# KeyboardMatrix.net
KiCad netlist of a schematic drawn in Altium Designer
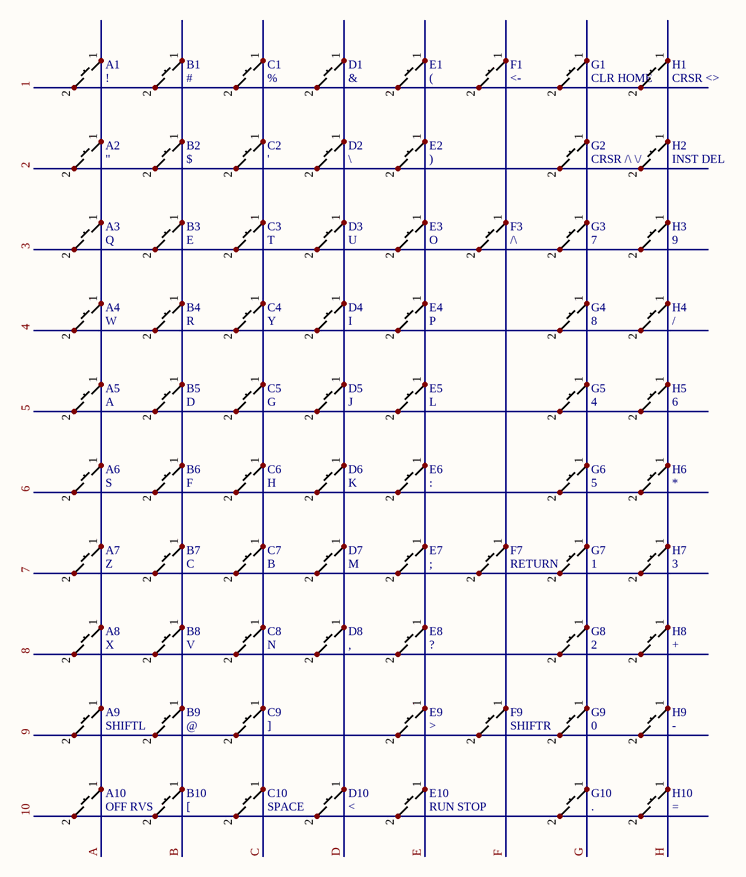
[diagram p0: KeyboardMatrix.SchDoc]

(export (version "E")
  (design (tool "Eeschema 10.0.6"))
  (components
    (comp (ref "A1")
      (value "!")
      (footprint "PET2001NKeyboardSoftButton")
      (libsource (lib "SomeParts") (part "PET2001NKeyboardSoftButton"))
    )
    (comp (ref "A2")
      (value "\"")
      (footprint "PET2001NKeyboardSoftButton")
      (libsource (lib "SomeParts") (part "PET2001NKeyboardSoftButton"))
    )
    (comp (ref "A3")
      (value "Q")
      (footprint "PET2001NKeyboardSoftButton")
      (libsource (lib "SomeParts") (part "PET2001NKeyboardSoftButton"))
    )
    (comp (ref "A4")
      (value "W")
      (footprint "PET2001NKeyboardSoftButton")
      (libsource (lib "SomeParts") (part "PET2001NKeyboardSoftButton"))
    )
    (comp (ref "A5")
      (value "A")
      (footprint "PET2001NKeyboardSoftButton")
      (libsource (lib "SomeParts") (part "PET2001NKeyboardSoftButton"))
    )
    (comp (ref "A6")
      (value "S")
      (footprint "PET2001NKeyboardSoftButton")
      (libsource (lib "SomeParts") (part "PET2001NKeyboardSoftButton"))
    )
    (comp (ref "A7")
      (value "Z")
      (footprint "PET2001NKeyboardSoftButton")
      (libsource (lib "SomeParts") (part "PET2001NKeyboardSoftButton"))
    )
    (comp (ref "A8")
      (value "X")
      (footprint "PET2001NKeyboardSoftButton")
      (libsource (lib "SomeParts") (part "PET2001NKeyboardSoftButton"))
    )
    (comp (ref "A9")
      (value "SHIFTL")
      (footprint "PET2001NKeyboardSoftButton")
      (libsource (lib "SomeParts") (part "PET2001NKeyboardSoftButton"))
    )
    (comp (ref "A10")
      (value "OFF RVS")
      (footprint "PET2001NKeyboardSoftButton")
      (libsource (lib "SomeParts") (part "PET2001NKeyboardSoftButton"))
    )
    (comp (ref "B1")
      (value "#")
      (footprint "PET2001NKeyboardSoftButton")
      (libsource (lib "SomeParts") (part "PET2001NKeyboardSoftButton"))
    )
    (comp (ref "B2")
      (value "$")
      (footprint "PET2001NKeyboardSoftButton")
      (libsource (lib "SomeParts") (part "PET2001NKeyboardSoftButton"))
    )
    (comp (ref "B3")
      (value "E")
      (footprint "PET2001NKeyboardSoftButton")
      (libsource (lib "SomeParts") (part "PET2001NKeyboardSoftButton"))
    )
    (comp (ref "B4")
      (value "R")
      (footprint "PET2001NKeyboardSoftButton")
      (libsource (lib "SomeParts") (part "PET2001NKeyboardSoftButton"))
    )
    (comp (ref "B5")
      (value "D")
      (footprint "PET2001NKeyboardSoftButton")
      (libsource (lib "SomeParts") (part "PET2001NKeyboardSoftButton"))
    )
    (comp (ref "B6")
      (value "F")
      (footprint "PET2001NKeyboardSoftButton")
      (libsource (lib "SomeParts") (part "PET2001NKeyboardSoftButton"))
    )
    (comp (ref "B7")
      (value "C")
      (footprint "PET2001NKeyboardSoftButton")
      (libsource (lib "SomeParts") (part "PET2001NKeyboardSoftButton"))
    )
    (comp (ref "B8")
      (value "V")
      (footprint "PET2001NKeyboardSoftButton")
      (libsource (lib "SomeParts") (part "PET2001NKeyboardSoftButton"))
    )
    (comp (ref "B9")
      (value "@")
      (footprint "PET2001NKeyboardSoftButton")
      (libsource (lib "SomeParts") (part "PET2001NKeyboardSoftButton"))
    )
    (comp (ref "B10")
      (value "[")
      (footprint "PET2001NKeyboardSoftButton")
      (libsource (lib "SomeParts") (part "PET2001NKeyboardSoftButton"))
    )
    (comp (ref "C1")
      (value "%")
      (footprint "PET2001NKeyboardSoftButton")
      (libsource (lib "SomeParts") (part "PET2001NKeyboardSoftButton"))
    )
    (comp (ref "C2")
      (value "'")
      (footprint "PET2001NKeyboardSoftButton")
      (libsource (lib "SomeParts") (part "PET2001NKeyboardSoftButton"))
    )
    (comp (ref "C3")
      (value "T")
      (footprint "PET2001NKeyboardSoftButton")
      (libsource (lib "SomeParts") (part "PET2001NKeyboardSoftButton"))
    )
    (comp (ref "C4")
      (value "Y")
      (footprint "PET2001NKeyboardSoftButton")
      (libsource (lib "SomeParts") (part "PET2001NKeyboardSoftButton"))
    )
    (comp (ref "C5")
      (value "G")
      (footprint "PET2001NKeyboardSoftButton")
      (libsource (lib "SomeParts") (part "PET2001NKeyboardSoftButton"))
    )
    (comp (ref "C6")
      (value "H")
      (footprint "PET2001NKeyboardSoftButton")
      (libsource (lib "SomeParts") (part "PET2001NKeyboardSoftButton"))
    )
    (comp (ref "C7")
      (value "B")
      (footprint "PET2001NKeyboardSoftButton")
      (libsource (lib "SomeParts") (part "PET2001NKeyboardSoftButton"))
    )
    (comp (ref "C8")
      (value "N")
      (footprint "PET2001NKeyboardSoftButton")
      (libsource (lib "SomeParts") (part "PET2001NKeyboardSoftButton"))
    )
    (comp (ref "C9")
      (value "]")
      (footprint "PET2001NKeyboardSoftButton")
      (libsource (lib "SomeParts") (part "PET2001NKeyboardSoftButton"))
    )
    (comp (ref "C10")
      (value "SPACE")
      (footprint "PET2001NKeyboardSoftButton")
      (libsource (lib "SomeParts") (part "PET2001NKeyboardSoftButton"))
    )
    (comp (ref "D1")
      (value "&")
      (footprint "PET2001NKeyboardSoftButton")
      (libsource (lib "SomeParts") (part "PET2001NKeyboardSoftButton"))
    )
    (comp (ref "D2")
      (value "\\")
      (footprint "PET2001NKeyboardSoftButton")
      (libsource (lib "SomeParts") (part "PET2001NKeyboardSoftButton"))
    )
    (comp (ref "D3")
      (value "U")
      (footprint "PET2001NKeyboardSoftButton")
      (libsource (lib "SomeParts") (part "PET2001NKeyboardSoftButton"))
    )
    (comp (ref "D4")
      (value "I")
      (footprint "PET2001NKeyboardSoftButton")
      (libsource (lib "SomeParts") (part "PET2001NKeyboardSoftButton"))
    )
    (comp (ref "D5")
      (value "J")
      (footprint "PET2001NKeyboardSoftButton")
      (libsource (lib "SomeParts") (part "PET2001NKeyboardSoftButton"))
    )
    (comp (ref "D6")
      (value "K")
      (footprint "PET2001NKeyboardSoftButton")
      (libsource (lib "SomeParts") (part "PET2001NKeyboardSoftButton"))
    )
    (comp (ref "D7")
      (value "M")
      (footprint "PET2001NKeyboardSoftButton")
      (libsource (lib "SomeParts") (part "PET2001NKeyboardSoftButton"))
    )
    (comp (ref "D8")
      (value ",")
      (footprint "PET2001NKeyboardSoftButton")
      (libsource (lib "SomeParts") (part "PET2001NKeyboardSoftButton"))
    )
    (comp (ref "D10")
      (value "<")
      (footprint "PET2001NKeyboardSoftButton")
      (libsource (lib "SomeParts") (part "PET2001NKeyboardSoftButton"))
    )
    (comp (ref "E1")
      (value "(")
      (footprint "PET2001NKeyboardSoftButton")
      (libsource (lib "SomeParts") (part "PET2001NKeyboardSoftButton"))
    )
    (comp (ref "E2")
      (value ")")
      (footprint "PET2001NKeyboardSoftButton")
      (libsource (lib "SomeParts") (part "PET2001NKeyboardSoftButton"))
    )
    (comp (ref "E3")
      (value "O")
      (footprint "PET2001NKeyboardSoftButton")
      (libsource (lib "SomeParts") (part "PET2001NKeyboardSoftButton"))
    )
    (comp (ref "E4")
      (value "P")
      (footprint "PET2001NKeyboardSoftButton")
      (libsource (lib "SomeParts") (part "PET2001NKeyboardSoftButton"))
    )
    (comp (ref "E5")
      (value "L")
      (footprint "PET2001NKeyboardSoftButton")
      (libsource (lib "SomeParts") (part "PET2001NKeyboardSoftButton"))
    )
    (comp (ref "E6")
      (value ":")
      (footprint "PET2001NKeyboardSoftButton")
      (libsource (lib "SomeParts") (part "PET2001NKeyboardSoftButton"))
    )
    (comp (ref "E7")
      (value ";")
      (footprint "PET2001NKeyboardSoftButton")
      (libsource (lib "SomeParts") (part "PET2001NKeyboardSoftButton"))
    )
    (comp (ref "E8")
      (value "?")
      (footprint "PET2001NKeyboardSoftButton")
      (libsource (lib "SomeParts") (part "PET2001NKeyboardSoftButton"))
    )
    (comp (ref "E9")
      (value ">")
      (footprint "PET2001NKeyboardSoftButton")
      (libsource (lib "SomeParts") (part "PET2001NKeyboardSoftButton"))
    )
    (comp (ref "E10")
      (value "RUN STOP")
      (footprint "PET2001NKeyboardSoftButton")
      (libsource (lib "SomeParts") (part "PET2001NKeyboardSoftButton"))
    )
    (comp (ref "F1")
      (value "<-")
      (footprint "PET2001NKeyboardSoftButton")
      (libsource (lib "SomeParts") (part "PET2001NKeyboardSoftButton"))
    )
    (comp (ref "F3")
      (value "~{/}")
      (footprint "PET2001NKeyboardSoftButton")
      (libsource (lib "SomeParts") (part "PET2001NKeyboardSoftButton"))
    )
    (comp (ref "F7")
      (value "RETURN")
      (footprint "PET2001NKeyboardSoftButton")
      (libsource (lib "SomeParts") (part "PET2001NKeyboardSoftButton"))
    )
    (comp (ref "F9")
      (value "SHIFTR")
      (footprint "PET2001NKeyboardSoftButton")
      (libsource (lib "SomeParts") (part "PET2001NKeyboardSoftButton"))
    )
    (comp (ref "G1")
      (value "CLR HOME")
      (footprint "PET2001NKeyboardSoftButton")
      (libsource (lib "SomeParts") (part "PET2001NKeyboardSoftButton"))
    )
    (comp (ref "G2")
      (value "CRSR ~{/ }/")
      (footprint "PET2001NKeyboardSoftButton")
      (libsource (lib "SomeParts") (part "PET2001NKeyboardSoftButton"))
    )
    (comp (ref "G3")
      (value "7")
      (footprint "PET2001NKeyboardSoftButton")
      (libsource (lib "SomeParts") (part "PET2001NKeyboardSoftButton"))
    )
    (comp (ref "G4")
      (value "8")
      (footprint "PET2001NKeyboardSoftButton")
      (libsource (lib "SomeParts") (part "PET2001NKeyboardSoftButton"))
    )
    (comp (ref "G5")
      (value "4")
      (footprint "PET2001NKeyboardSoftButton")
      (libsource (lib "SomeParts") (part "PET2001NKeyboardSoftButton"))
    )
    (comp (ref "G6")
      (value "5")
      (footprint "PET2001NKeyboardSoftButton")
      (libsource (lib "SomeParts") (part "PET2001NKeyboardSoftButton"))
    )
    (comp (ref "G7")
      (value "1")
      (footprint "PET2001NKeyboardSoftButton")
      (libsource (lib "SomeParts") (part "PET2001NKeyboardSoftButton"))
    )
    (comp (ref "G8")
      (value "2")
      (footprint "PET2001NKeyboardSoftButton")
      (libsource (lib "SomeParts") (part "PET2001NKeyboardSoftButton"))
    )
    (comp (ref "G9")
      (value "0")
      (footprint "PET2001NKeyboardSoftButton")
      (libsource (lib "SomeParts") (part "PET2001NKeyboardSoftButton"))
    )
    (comp (ref "G10")
      (value ".")
      (footprint "PET2001NKeyboardSoftButton")
      (libsource (lib "SomeParts") (part "PET2001NKeyboardSoftButton"))
    )
    (comp (ref "H1")
      (value "CRSR <>")
      (footprint "PET2001NKeyboardSoftButton")
      (libsource (lib "SomeParts") (part "PET2001NKeyboardSoftButton"))
    )
    (comp (ref "H2")
      (value "INST DEL")
      (footprint "PET2001NKeyboardSoftButton")
      (libsource (lib "SomeParts") (part "PET2001NKeyboardSoftButton"))
    )
    (comp (ref "H3")
      (value "9")
      (footprint "PET2001NKeyboardSoftButton")
      (libsource (lib "SomeParts") (part "PET2001NKeyboardSoftButton"))
    )
    (comp (ref "H4")
      (value "/")
      (footprint "PET2001NKeyboardSoftButton")
      (libsource (lib "SomeParts") (part "PET2001NKeyboardSoftButton"))
    )
    (comp (ref "H5")
      (value "6")
      (footprint "PET2001NKeyboardSoftButton")
      (libsource (lib "SomeParts") (part "PET2001NKeyboardSoftButton"))
    )
    (comp (ref "H6")
      (value "*")
      (footprint "PET2001NKeyboardSoftButton")
      (libsource (lib "SomeParts") (part "PET2001NKeyboardSoftButton"))
    )
    (comp (ref "H7")
      (value "3")
      (footprint "PET2001NKeyboardSoftButton")
      (libsource (lib "SomeParts") (part "PET2001NKeyboardSoftButton"))
    )
    (comp (ref "H8")
      (value "+")
      (footprint "PET2001NKeyboardSoftButton")
      (libsource (lib "SomeParts") (part "PET2001NKeyboardSoftButton"))
    )
    (comp (ref "H9")
      (value "-")
      (footprint "PET2001NKeyboardSoftButton")
      (libsource (lib "SomeParts") (part "PET2001NKeyboardSoftButton"))
    )
    (comp (ref "H10")
      (value "~")
      (footprint "PET2001NKeyboardSoftButton")
      (libsource (lib "SomeParts") (part "PET2001NKeyboardSoftButton"))
    )
  )
  (nets
    (net (code "1") (name "/1") (class "Default")
      (node (ref "A1") (pin "2") (pinfunction "2_2") (pintype "passive"))
      (node (ref "B1") (pin "2") (pinfunction "2_2") (pintype "passive"))
      (node (ref "C1") (pin "2") (pinfunction "2_2") (pintype "passive"))
      (node (ref "D1") (pin "2") (pinfunction "2_2") (pintype "passive"))
      (node (ref "E1") (pin "2") (pinfunction "2_2") (pintype "passive"))
      (node (ref "F1") (pin "2") (pinfunction "2_2") (pintype "passive"))
      (node (ref "G1") (pin "2") (pinfunction "2_2") (pintype "passive"))
      (node (ref "H1") (pin "2") (pinfunction "2_2") (pintype "passive"))
    )
    (net (code "2") (name "/2") (class "Default")
      (node (ref "A2") (pin "2") (pinfunction "2_2") (pintype "passive"))
      (node (ref "B2") (pin "2") (pinfunction "2_2") (pintype "passive"))
      (node (ref "C2") (pin "2") (pinfunction "2_2") (pintype "passive"))
      (node (ref "D2") (pin "2") (pinfunction "2_2") (pintype "passive"))
      (node (ref "E2") (pin "2") (pinfunction "2_2") (pintype "passive"))
      (node (ref "G2") (pin "2") (pinfunction "2_2") (pintype "passive"))
      (node (ref "H2") (pin "2") (pinfunction "2_2") (pintype "passive"))
    )
    (net (code "3") (name "/3") (class "Default")
      (node (ref "A3") (pin "2") (pinfunction "2_2") (pintype "passive"))
      (node (ref "B3") (pin "2") (pinfunction "2_2") (pintype "passive"))
      (node (ref "C3") (pin "2") (pinfunction "2_2") (pintype "passive"))
      (node (ref "D3") (pin "2") (pinfunction "2_2") (pintype "passive"))
      (node (ref "E3") (pin "2") (pinfunction "2_2") (pintype "passive"))
      (node (ref "F3") (pin "2") (pinfunction "2_2") (pintype "passive"))
      (node (ref "G3") (pin "2") (pinfunction "2_2") (pintype "passive"))
      (node (ref "H3") (pin "2") (pinfunction "2_2") (pintype "passive"))
    )
    (net (code "4") (name "/4") (class "Default")
      (node (ref "A4") (pin "2") (pinfunction "2_2") (pintype "passive"))
      (node (ref "B4") (pin "2") (pinfunction "2_2") (pintype "passive"))
      (node (ref "C4") (pin "2") (pinfunction "2_2") (pintype "passive"))
      (node (ref "D4") (pin "2") (pinfunction "2_2") (pintype "passive"))
      (node (ref "E4") (pin "2") (pinfunction "2_2") (pintype "passive"))
      (node (ref "G4") (pin "2") (pinfunction "2_2") (pintype "passive"))
      (node (ref "H4") (pin "2") (pinfunction "2_2") (pintype "passive"))
    )
    (net (code "5") (name "/5") (class "Default")
      (node (ref "A5") (pin "2") (pinfunction "2_2") (pintype "passive"))
      (node (ref "B5") (pin "2") (pinfunction "2_2") (pintype "passive"))
      (node (ref "C5") (pin "2") (pinfunction "2_2") (pintype "passive"))
      (node (ref "D5") (pin "2") (pinfunction "2_2") (pintype "passive"))
      (node (ref "E5") (pin "2") (pinfunction "2_2") (pintype "passive"))
      (node (ref "G5") (pin "2") (pinfunction "2_2") (pintype "passive"))
      (node (ref "H5") (pin "2") (pinfunction "2_2") (pintype "passive"))
    )
    (net (code "6") (name "/6") (class "Default")
      (node (ref "A6") (pin "2") (pinfunction "2_2") (pintype "passive"))
      (node (ref "B6") (pin "2") (pinfunction "2_2") (pintype "passive"))
      (node (ref "C6") (pin "2") (pinfunction "2_2") (pintype "passive"))
      (node (ref "D6") (pin "2") (pinfunction "2_2") (pintype "passive"))
      (node (ref "E6") (pin "2") (pinfunction "2_2") (pintype "passive"))
      (node (ref "G6") (pin "2") (pinfunction "2_2") (pintype "passive"))
      (node (ref "H6") (pin "2") (pinfunction "2_2") (pintype "passive"))
    )
    (net (code "7") (name "/7") (class "Default")
      (node (ref "A7") (pin "2") (pinfunction "2_2") (pintype "passive"))
      (node (ref "B7") (pin "2") (pinfunction "2_2") (pintype "passive"))
      (node (ref "C7") (pin "2") (pinfunction "2_2") (pintype "passive"))
      (node (ref "D7") (pin "2") (pinfunction "2_2") (pintype "passive"))
      (node (ref "E7") (pin "2") (pinfunction "2_2") (pintype "passive"))
      (node (ref "F7") (pin "2") (pinfunction "2_2") (pintype "passive"))
      (node (ref "G7") (pin "2") (pinfunction "2_2") (pintype "passive"))
      (node (ref "H7") (pin "2") (pinfunction "2_2") (pintype "passive"))
    )
    (net (code "8") (name "/8") (class "Default")
      (node (ref "A8") (pin "2") (pinfunction "2_2") (pintype "passive"))
      (node (ref "B8") (pin "2") (pinfunction "2_2") (pintype "passive"))
      (node (ref "C8") (pin "2") (pinfunction "2_2") (pintype "passive"))
      (node (ref "D8") (pin "2") (pinfunction "2_2") (pintype "passive"))
      (node (ref "E8") (pin "2") (pinfunction "2_2") (pintype "passive"))
      (node (ref "G8") (pin "2") (pinfunction "2_2") (pintype "passive"))
      (node (ref "H8") (pin "2") (pinfunction "2_2") (pintype "passive"))
    )
    (net (code "9") (name "/9") (class "Default")
      (node (ref "A9") (pin "2") (pinfunction "2_2") (pintype "passive"))
      (node (ref "B9") (pin "2") (pinfunction "2_2") (pintype "passive"))
      (node (ref "C9") (pin "2") (pinfunction "2_2") (pintype "passive"))
      (node (ref "E9") (pin "2") (pinfunction "2_2") (pintype "passive"))
      (node (ref "F9") (pin "2") (pinfunction "2_2") (pintype "passive"))
      (node (ref "G9") (pin "2") (pinfunction "2_2") (pintype "passive"))
      (node (ref "H9") (pin "2") (pinfunction "2_2") (pintype "passive"))
    )
    (net (code "10") (name "/10") (class "Default")
      (node (ref "A10") (pin "2") (pinfunction "2_2") (pintype "passive"))
      (node (ref "B10") (pin "2") (pinfunction "2_2") (pintype "passive"))
      (node (ref "C10") (pin "2") (pinfunction "2_2") (pintype "passive"))
      (node (ref "D10") (pin "2") (pinfunction "2_2") (pintype "passive"))
      (node (ref "E10") (pin "2") (pinfunction "2_2") (pintype "passive"))
      (node (ref "G10") (pin "2") (pinfunction "2_2") (pintype "passive"))
      (node (ref "H10") (pin "2") (pinfunction "2_2") (pintype "passive"))
    )
    (net (code "11") (name "/A") (class "Default")
      (node (ref "A1") (pin "1") (pinfunction "1_1") (pintype "passive"))
      (node (ref "A10") (pin "1") (pinfunction "1_1") (pintype "passive"))
      (node (ref "A2") (pin "1") (pinfunction "1_1") (pintype "passive"))
      (node (ref "A3") (pin "1") (pinfunction "1_1") (pintype "passive"))
      (node (ref "A4") (pin "1") (pinfunction "1_1") (pintype "passive"))
      (node (ref "A5") (pin "1") (pinfunction "1_1") (pintype "passive"))
      (node (ref "A6") (pin "1") (pinfunction "1_1") (pintype "passive"))
      (node (ref "A7") (pin "1") (pinfunction "1_1") (pintype "passive"))
      (node (ref "A8") (pin "1") (pinfunction "1_1") (pintype "passive"))
      (node (ref "A9") (pin "1") (pinfunction "1_1") (pintype "passive"))
    )
    (net (code "12") (name "/B") (class "Default")
      (node (ref "B1") (pin "1") (pinfunction "1_1") (pintype "passive"))
      (node (ref "B10") (pin "1") (pinfunction "1_1") (pintype "passive"))
      (node (ref "B2") (pin "1") (pinfunction "1_1") (pintype "passive"))
      (node (ref "B3") (pin "1") (pinfunction "1_1") (pintype "passive"))
      (node (ref "B4") (pin "1") (pinfunction "1_1") (pintype "passive"))
      (node (ref "B5") (pin "1") (pinfunction "1_1") (pintype "passive"))
      (node (ref "B6") (pin "1") (pinfunction "1_1") (pintype "passive"))
      (node (ref "B7") (pin "1") (pinfunction "1_1") (pintype "passive"))
      (node (ref "B8") (pin "1") (pinfunction "1_1") (pintype "passive"))
      (node (ref "B9") (pin "1") (pinfunction "1_1") (pintype "passive"))
    )
    (net (code "13") (name "/C") (class "Default")
      (node (ref "C1") (pin "1") (pinfunction "1_1") (pintype "passive"))
      (node (ref "C10") (pin "1") (pinfunction "1_1") (pintype "passive"))
      (node (ref "C2") (pin "1") (pinfunction "1_1") (pintype "passive"))
      (node (ref "C3") (pin "1") (pinfunction "1_1") (pintype "passive"))
      (node (ref "C4") (pin "1") (pinfunction "1_1") (pintype "passive"))
      (node (ref "C5") (pin "1") (pinfunction "1_1") (pintype "passive"))
      (node (ref "C6") (pin "1") (pinfunction "1_1") (pintype "passive"))
      (node (ref "C7") (pin "1") (pinfunction "1_1") (pintype "passive"))
      (node (ref "C8") (pin "1") (pinfunction "1_1") (pintype "passive"))
      (node (ref "C9") (pin "1") (pinfunction "1_1") (pintype "passive"))
    )
    (net (code "14") (name "/D") (class "Default")
      (node (ref "D1") (pin "1") (pinfunction "1_1") (pintype "passive"))
      (node (ref "D10") (pin "1") (pinfunction "1_1") (pintype "passive"))
      (node (ref "D2") (pin "1") (pinfunction "1_1") (pintype "passive"))
      (node (ref "D3") (pin "1") (pinfunction "1_1") (pintype "passive"))
      (node (ref "D4") (pin "1") (pinfunction "1_1") (pintype "passive"))
      (node (ref "D5") (pin "1") (pinfunction "1_1") (pintype "passive"))
      (node (ref "D6") (pin "1") (pinfunction "1_1") (pintype "passive"))
      (node (ref "D7") (pin "1") (pinfunction "1_1") (pintype "passive"))
      (node (ref "D8") (pin "1") (pinfunction "1_1") (pintype "passive"))
    )
    (net (code "15") (name "/E") (class "Default")
      (node (ref "E1") (pin "1") (pinfunction "1_1") (pintype "passive"))
      (node (ref "E10") (pin "1") (pinfunction "1_1") (pintype "passive"))
      (node (ref "E2") (pin "1") (pinfunction "1_1") (pintype "passive"))
      (node (ref "E3") (pin "1") (pinfunction "1_1") (pintype "passive"))
      (node (ref "E4") (pin "1") (pinfunction "1_1") (pintype "passive"))
      (node (ref "E5") (pin "1") (pinfunction "1_1") (pintype "passive"))
      (node (ref "E6") (pin "1") (pinfunction "1_1") (pintype "passive"))
      (node (ref "E7") (pin "1") (pinfunction "1_1") (pintype "passive"))
      (node (ref "E8") (pin "1") (pinfunction "1_1") (pintype "passive"))
      (node (ref "E9") (pin "1") (pinfunction "1_1") (pintype "passive"))
    )
    (net (code "16") (name "/F") (class "Default")
      (node (ref "F1") (pin "1") (pinfunction "1_1") (pintype "passive"))
      (node (ref "F3") (pin "1") (pinfunction "1_1") (pintype "passive"))
      (node (ref "F7") (pin "1") (pinfunction "1_1") (pintype "passive"))
      (node (ref "F9") (pin "1") (pinfunction "1_1") (pintype "passive"))
    )
    (net (code "17") (name "/G") (class "Default")
      (node (ref "G1") (pin "1") (pinfunction "1_1") (pintype "passive"))
      (node (ref "G10") (pin "1") (pinfunction "1_1") (pintype "passive"))
      (node (ref "G2") (pin "1") (pinfunction "1_1") (pintype "passive"))
      (node (ref "G3") (pin "1") (pinfunction "1_1") (pintype "passive"))
      (node (ref "G4") (pin "1") (pinfunction "1_1") (pintype "passive"))
      (node (ref "G5") (pin "1") (pinfunction "1_1") (pintype "passive"))
      (node (ref "G6") (pin "1") (pinfunction "1_1") (pintype "passive"))
      (node (ref "G7") (pin "1") (pinfunction "1_1") (pintype "passive"))
      (node (ref "G8") (pin "1") (pinfunction "1_1") (pintype "passive"))
      (node (ref "G9") (pin "1") (pinfunction "1_1") (pintype "passive"))
    )
    (net (code "18") (name "/H") (class "Default")
      (node (ref "H1") (pin "1") (pinfunction "1_1") (pintype "passive"))
      (node (ref "H10") (pin "1") (pinfunction "1_1") (pintype "passive"))
      (node (ref "H2") (pin "1") (pinfunction "1_1") (pintype "passive"))
      (node (ref "H3") (pin "1") (pinfunction "1_1") (pintype "passive"))
      (node (ref "H4") (pin "1") (pinfunction "1_1") (pintype "passive"))
      (node (ref "H5") (pin "1") (pinfunction "1_1") (pintype "passive"))
      (node (ref "H6") (pin "1") (pinfunction "1_1") (pintype "passive"))
      (node (ref "H7") (pin "1") (pinfunction "1_1") (pintype "passive"))
      (node (ref "H8") (pin "1") (pinfunction "1_1") (pintype "passive"))
      (node (ref "H9") (pin "1") (pinfunction "1_1") (pintype "passive"))
    )
  )
)
